# generic_midi_1.net
KiCad netlist of a schematic drawn in EAGLE
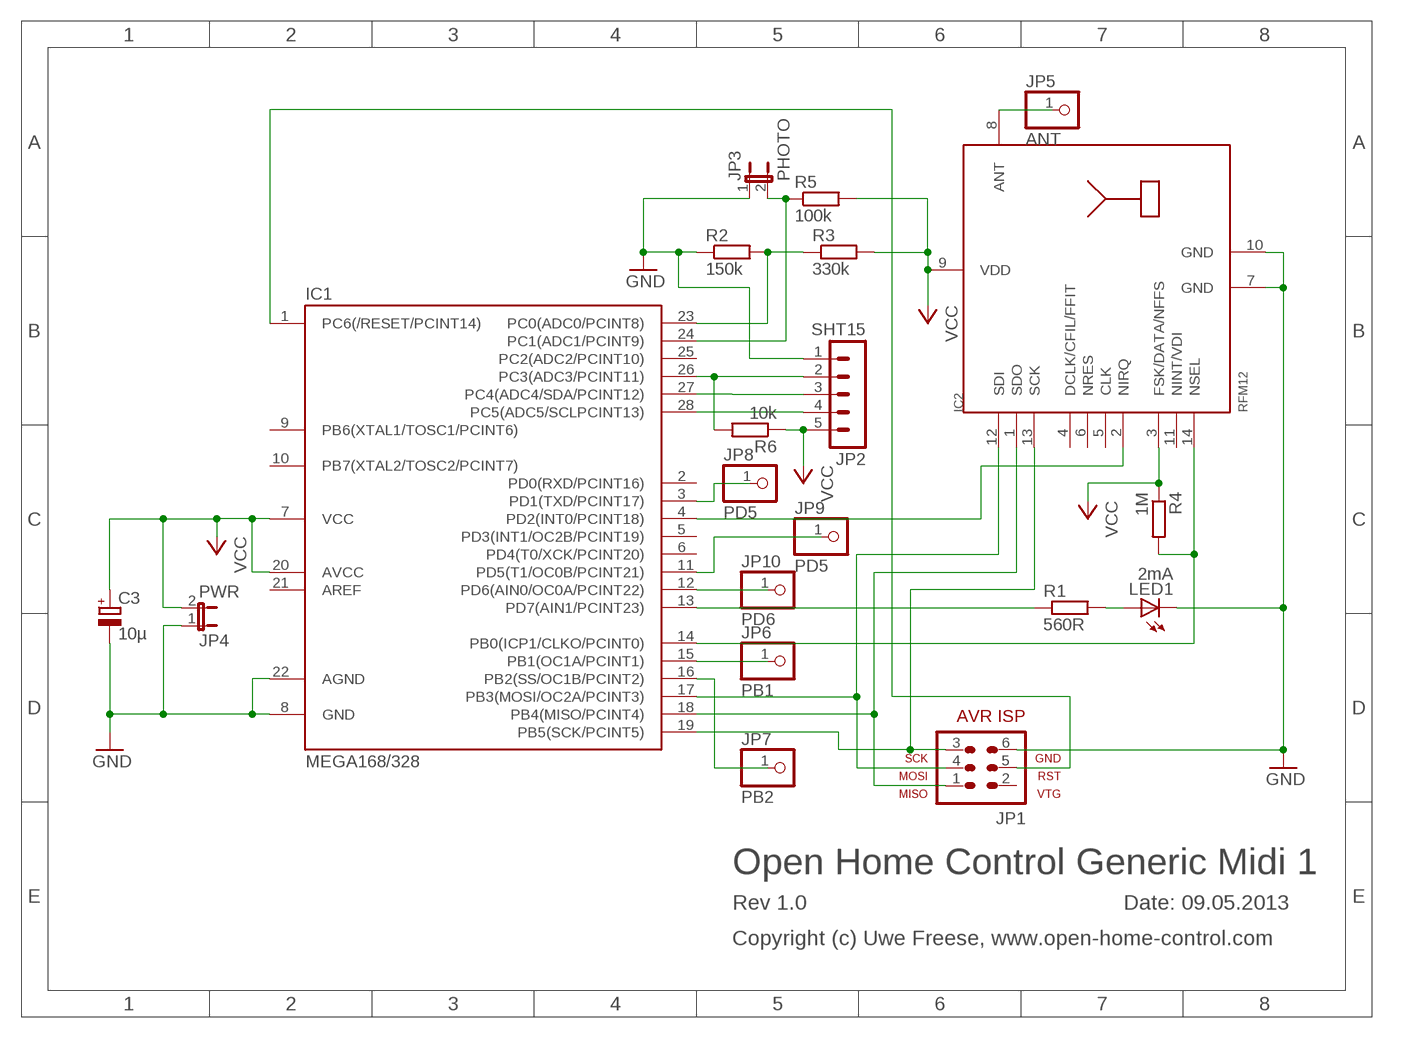
[diagram p0: schematic, sheet 1]

(export (version "E")
  (design (tool "Eeschema 10.0.6"))
  (components
    (comp (ref "C3")
      (value "10µ")
      (footprint "eagle-import:E1,8-4")
      (libsource (lib "eagle-import") (part "CPOL-EUE1.8-4"))
    )
    (comp (ref "IC1")
      (value "MEGA168/328")
      (footprint "eagle-import:DIL28-3")
      (libsource (lib "eagle-import") (part "MEGA48/88/168-PU"))
    )
    (comp (ref "IC2")
      (value "RFM12")
      (footprint "eagle-import:RFM")
      (libsource (lib "eagle-import") (part "RFM12"))
    )
    (comp (ref "JP1")
      (value "AVR-ISP-6")
      (footprint "eagle-import:AVR-ISP-6")
      (libsource (lib "eagle-import") (part "AVR-ISP-6"))
    )
    (comp (ref "JP2")
      (value "SHT15")
      (footprint "eagle-import:MA05-1")
      (libsource (lib "eagle-import") (part "MA05-1"))
    )
    (comp (ref "JP3")
      (value "PHOTO")
      (footprint "eagle-import:JP1")
      (libsource (lib "eagle-import") (part "JP1E"))
    )
    (comp (ref "JP4")
      (value "PWR")
      (footprint "eagle-import:JP1")
      (libsource (lib "eagle-import") (part "JP1E"))
    )
    (comp (ref "JP5")
      (value "ANT")
      (footprint "eagle-import:1X01")
      (libsource (lib "eagle-import") (part "PINHD-1X1"))
    )
    (comp (ref "JP6")
      (value "PB1")
      (footprint "eagle-import:1X01")
      (libsource (lib "eagle-import") (part "PINHD-1X1"))
    )
    (comp (ref "JP7")
      (value "PB2")
      (footprint "eagle-import:1X01")
      (libsource (lib "eagle-import") (part "PINHD-1X1"))
    )
    (comp (ref "JP8")
      (value "PD5")
      (footprint "eagle-import:1X01")
      (libsource (lib "eagle-import") (part "PINHD-1X1"))
    )
    (comp (ref "JP9")
      (value "PD5")
      (footprint "eagle-import:1X01")
      (libsource (lib "eagle-import") (part "PINHD-1X1"))
    )
    (comp (ref "JP10")
      (value "PD6")
      (footprint "eagle-import:1X01")
      (libsource (lib "eagle-import") (part "PINHD-1X1"))
    )
    (comp (ref "LED1")
      (value "2mA")
      (footprint "eagle-import:LED3MM")
      (libsource (lib "eagle-import") (part "LED3MM"))
    )
    (comp (ref "R1")
      (value "560R")
      (footprint "eagle-import:0207_7")
      (libsource (lib "eagle-import") (part "R-EU_0207/7"))
    )
    (comp (ref "R2")
      (value "150k")
      (footprint "eagle-import:0207_7")
      (libsource (lib "eagle-import") (part "R-EU_0207/7"))
    )
    (comp (ref "R3")
      (value "330k")
      (footprint "eagle-import:0207_7")
      (libsource (lib "eagle-import") (part "R-EU_0207/7"))
    )
    (comp (ref "R4")
      (value "1M")
      (footprint "eagle-import:0207_7")
      (libsource (lib "eagle-import") (part "R-EU_0207/7"))
    )
    (comp (ref "R5")
      (value "100k")
      (footprint "eagle-import:0207_7")
      (libsource (lib "eagle-import") (part "R-EU_0207/7"))
    )
    (comp (ref "R6")
      (value "10k")
      (footprint "eagle-import:0207_7")
      (libsource (lib "eagle-import") (part "R-EU_0207/7"))
    )
  )
  (nets
    (net (code "1") (name "GND") (class "Default")
      (node (ref "C3") (pin "-") (pinfunction "-_-") (pintype "passive"))
      (node (ref "IC1") (pin "22") (pinfunction "AGND_22") (pintype "power_in"))
      (node (ref "IC1") (pin "8") (pinfunction "GND_8") (pintype "power_in"))
      (node (ref "IC2") (pin "10") (pinfunction "GND_10") (pintype "power_in"))
      (node (ref "IC2") (pin "7") (pinfunction "GND_7") (pintype "power_in"))
      (node (ref "JP1") (pin "6") (pinfunction "6_6") (pintype "passive"))
      (node (ref "JP2") (pin "1") (pinfunction "1_1") (pintype "passive"))
      (node (ref "JP3") (pin "1") (pinfunction "1_1") (pintype "passive"))
      (node (ref "JP4") (pin "1") (pinfunction "1_1") (pintype "passive"))
      (node (ref "LED1") (pin "K") (pinfunction "C_K") (pintype "passive"))
      (node (ref "R2") (pin "1") (pinfunction "1_1") (pintype "passive"))
    )
    (net (code "2") (name "Net-(IC1-PB0(ICP1{slash}CLKO{slash}PCINT0))") (class "Default")
      (node (ref "IC1") (pin "14") (pinfunction "PB0(ICP1/CLKO/PCINT0)_14") (pintype "bidirectional"))
      (node (ref "IC2") (pin "14") (pinfunction "NSEL_14") (pintype "bidirectional"))
      (node (ref "R4") (pin "2") (pinfunction "2_2") (pintype "passive"))
    )
    (net (code "3") (name "Net-(IC1-PB1(OC1A{slash}PCINT1))") (class "Default")
      (node (ref "IC1") (pin "15") (pinfunction "PB1(OC1A/PCINT1)_15") (pintype "bidirectional"))
      (node (ref "JP6") (pin "1") (pinfunction "1_1") (pintype "passive"))
    )
    (net (code "4") (name "Net-(IC1-PB2(SS{slash}OC1B{slash}PCINT2))") (class "Default")
      (node (ref "IC1") (pin "16") (pinfunction "PB2(SS/OC1B/PCINT2)_16") (pintype "bidirectional"))
      (node (ref "JP7") (pin "1") (pinfunction "1_1") (pintype "passive"))
    )
    (net (code "5") (name "Net-(IC1-PB3(MOSI{slash}OC2A{slash}PCINT3))") (class "Default")
      (node (ref "IC1") (pin "17") (pinfunction "PB3(MOSI/OC2A/PCINT3)_17") (pintype "bidirectional"))
      (node (ref "IC2") (pin "12") (pinfunction "SDI_12") (pintype "bidirectional"))
      (node (ref "JP1") (pin "4") (pinfunction "4_4") (pintype "passive"))
    )
    (net (code "6") (name "Net-(IC1-PB4(MISO{slash}PCINT4))") (class "Default")
      (node (ref "IC1") (pin "18") (pinfunction "PB4(MISO/PCINT4)_18") (pintype "bidirectional"))
      (node (ref "IC2") (pin "1") (pinfunction "SDO_1") (pintype "bidirectional"))
      (node (ref "JP1") (pin "1") (pinfunction "1_1") (pintype "passive"))
    )
    (net (code "7") (name "Net-(IC1-PB5(SCK{slash}PCINT5))") (class "Default")
      (node (ref "IC1") (pin "19") (pinfunction "PB5(SCK/PCINT5)_19") (pintype "bidirectional"))
      (node (ref "IC2") (pin "13") (pinfunction "SCK_13") (pintype "bidirectional"))
      (node (ref "JP1") (pin "3") (pinfunction "3_3") (pintype "passive"))
    )
    (net (code "8") (name "Net-(IC1-PC0(ADC0{slash}PCINT8))") (class "Default")
      (node (ref "IC1") (pin "23") (pinfunction "PC0(ADC0/PCINT8)_23") (pintype "bidirectional"))
      (node (ref "R2") (pin "2") (pinfunction "2_2") (pintype "passive"))
      (node (ref "R3") (pin "1") (pinfunction "1_1") (pintype "passive"))
    )
    (net (code "9") (name "Net-(IC1-PC1(ADC1{slash}PCINT9))") (class "Default")
      (node (ref "IC1") (pin "24") (pinfunction "PC1(ADC1/PCINT9)_24") (pintype "bidirectional"))
      (node (ref "JP3") (pin "2") (pinfunction "2_2") (pintype "passive"))
      (node (ref "R5") (pin "1") (pinfunction "1_1") (pintype "passive"))
    )
    (net (code "10") (name "Net-(IC1-PC3(ADC3{slash}PCINT11))") (class "Default")
      (node (ref "IC1") (pin "26") (pinfunction "PC3(ADC3/PCINT11)_26") (pintype "bidirectional"))
      (node (ref "JP2") (pin "2") (pinfunction "2_2") (pintype "passive"))
      (node (ref "R6") (pin "2") (pinfunction "2_2") (pintype "passive"))
    )
    (net (code "11") (name "Net-(IC1-PC4(ADC4{slash}SDA{slash}PCINT12))") (class "Default")
      (node (ref "IC1") (pin "27") (pinfunction "PC4(ADC4/SDA/PCINT12)_27") (pintype "bidirectional"))
      (node (ref "JP2") (pin "3") (pinfunction "3_3") (pintype "passive"))
    )
    (net (code "12") (name "Net-(IC1-PC5(ADC5{slash}SCLPCINT13))") (class "Default")
      (node (ref "IC1") (pin "28") (pinfunction "PC5(ADC5/SCLPCINT13)_28") (pintype "bidirectional"))
      (node (ref "JP2") (pin "4") (pinfunction "4_4") (pintype "passive"))
    )
    (net (code "13") (name "Net-(IC1-PC6({slash}RESET{slash}PCINT14))") (class "Default")
      (node (ref "IC1") (pin "1") (pinfunction "PC6(/RESET/PCINT14)_1") (pintype "bidirectional"))
      (node (ref "JP1") (pin "5") (pinfunction "5_5") (pintype "passive"))
    )
    (net (code "14") (name "Net-(IC1-PD1(TXD{slash}PCINT17))") (class "Default")
      (node (ref "IC1") (pin "3") (pinfunction "PD1(TXD/PCINT17)_3") (pintype "bidirectional"))
      (node (ref "JP8") (pin "1") (pinfunction "1_1") (pintype "passive"))
    )
    (net (code "15") (name "Net-(IC1-PD2(INT0{slash}PCINT18))") (class "Default")
      (node (ref "IC1") (pin "4") (pinfunction "PD2(INT0/PCINT18)_4") (pintype "bidirectional"))
      (node (ref "IC2") (pin "2") (pinfunction "NIRQ_2") (pintype "bidirectional"))
    )
    (net (code "16") (name "Net-(IC1-PD5(T1{slash}OC0B{slash}PCINT21))") (class "Default")
      (node (ref "IC1") (pin "11") (pinfunction "PD5(T1/OC0B/PCINT21)_11") (pintype "bidirectional"))
      (node (ref "JP9") (pin "1") (pinfunction "1_1") (pintype "passive"))
    )
    (net (code "17") (name "Net-(IC1-PD6(AIN0{slash}OC0A{slash}PCINT22))") (class "Default")
      (node (ref "IC1") (pin "12") (pinfunction "PD6(AIN0/OC0A/PCINT22)_12") (pintype "bidirectional"))
      (node (ref "JP10") (pin "1") (pinfunction "1_1") (pintype "passive"))
    )
    (net (code "18") (name "Net-(IC1-PD7(AIN1{slash}PCINT23))") (class "Default")
      (node (ref "IC1") (pin "13") (pinfunction "PD7(AIN1/PCINT23)_13") (pintype "bidirectional"))
      (node (ref "R1") (pin "1") (pinfunction "1_1") (pintype "passive"))
    )
    (net (code "19") (name "Net-(IC2-ANT)") (class "Default")
      (node (ref "IC2") (pin "8") (pinfunction "ANT_8") (pintype "output"))
      (node (ref "JP5") (pin "1") (pinfunction "1_1") (pintype "passive"))
    )
    (net (code "20") (name "Net-(LED1-PadA)") (class "Default")
      (node (ref "LED1") (pin "A") (pinfunction "A_A") (pintype "passive"))
      (node (ref "R1") (pin "2") (pinfunction "2_2") (pintype "passive"))
    )
    (net (code "21") (name "VCC") (class "Default")
      (node (ref "C3") (pin "+") (pinfunction "+_+") (pintype "passive"))
      (node (ref "IC1") (pin "20") (pinfunction "AVCC_20") (pintype "passive"))
      (node (ref "IC1") (pin "7") (pinfunction "VCC_7") (pintype "power_in"))
      (node (ref "IC2") (pin "3") (pinfunction "FSK/DATA/NFFS_3") (pintype "bidirectional"))
      (node (ref "IC2") (pin "9") (pinfunction "VDD_9") (pintype "power_in"))
      (node (ref "JP2") (pin "5") (pinfunction "5_5") (pintype "passive"))
      (node (ref "JP4") (pin "2") (pinfunction "2_2") (pintype "passive"))
      (node (ref "R3") (pin "2") (pinfunction "2_2") (pintype "passive"))
      (node (ref "R4") (pin "1") (pinfunction "1_1") (pintype "passive"))
      (node (ref "R5") (pin "2") (pinfunction "2_2") (pintype "passive"))
      (node (ref "R6") (pin "1") (pinfunction "1_1") (pintype "passive"))
    )
    (net (code "22") (name "unconnected-(IC1-AREF-Pad21)") (class "Default")
      (node (ref "IC1") (pin "21") (pinfunction "AREF_21") (pintype "passive"))
    )
    (net (code "23") (name "unconnected-(IC1-PB6(XTAL1{slash}TOSC1{slash}PCINT6)-Pad9)") (class "Default")
      (node (ref "IC1") (pin "9") (pinfunction "PB6(XTAL1/TOSC1/PCINT6)_9") (pintype "bidirectional"))
    )
    (net (code "24") (name "unconnected-(IC1-PB7(XTAL2{slash}TOSC2{slash}PCINT7)-Pad10)") (class "Default")
      (node (ref "IC1") (pin "10") (pinfunction "PB7(XTAL2/TOSC2/PCINT7)_10") (pintype "bidirectional"))
    )
    (net (code "25") (name "unconnected-(IC1-PC2(ADC2{slash}PCINT10)-Pad25)") (class "Default")
      (node (ref "IC1") (pin "25") (pinfunction "PC2(ADC2/PCINT10)_25") (pintype "bidirectional"))
    )
    (net (code "26") (name "unconnected-(IC1-PD0(RXD{slash}PCINT16)-Pad2)") (class "Default")
      (node (ref "IC1") (pin "2") (pinfunction "PD0(RXD/PCINT16)_2") (pintype "bidirectional"))
    )
    (net (code "27") (name "unconnected-(IC1-PD3(INT1{slash}OC2B{slash}PCINT19)-Pad5)") (class "Default")
      (node (ref "IC1") (pin "5") (pinfunction "PD3(INT1/OC2B/PCINT19)_5") (pintype "bidirectional"))
    )
    (net (code "28") (name "unconnected-(IC1-PD4(T0{slash}XCK{slash}PCINT20)-Pad6)") (class "Default")
      (node (ref "IC1") (pin "6") (pinfunction "PD4(T0/XCK/PCINT20)_6") (pintype "bidirectional"))
    )
    (net (code "29") (name "unconnected-(IC2-CLK-Pad5)") (class "Default")
      (node (ref "IC2") (pin "5") (pinfunction "CLK_5") (pintype "bidirectional"))
    )
    (net (code "30") (name "unconnected-(IC2-DCLK{slash}CFIL{slash}FFIT-Pad4)") (class "Default")
      (node (ref "IC2") (pin "4") (pinfunction "DCLK/CFIL/FFIT_4") (pintype "bidirectional"))
    )
    (net (code "31") (name "unconnected-(IC2-NINT{slash}VDI-Pad11)") (class "Default")
      (node (ref "IC2") (pin "11") (pinfunction "NINT/VDI_11") (pintype "bidirectional"))
    )
    (net (code "32") (name "unconnected-(IC2-NRES-Pad6)") (class "Default")
      (node (ref "IC2") (pin "6") (pinfunction "NRES_6") (pintype "bidirectional"))
    )
    (net (code "33") (name "unconnected-(JP1-Pad2)") (class "Default")
      (node (ref "JP1") (pin "2") (pinfunction "2_2") (pintype "passive"))
    )
  )
)
